# TPM.net
KiCad netlist of a schematic drawn in EAGLE
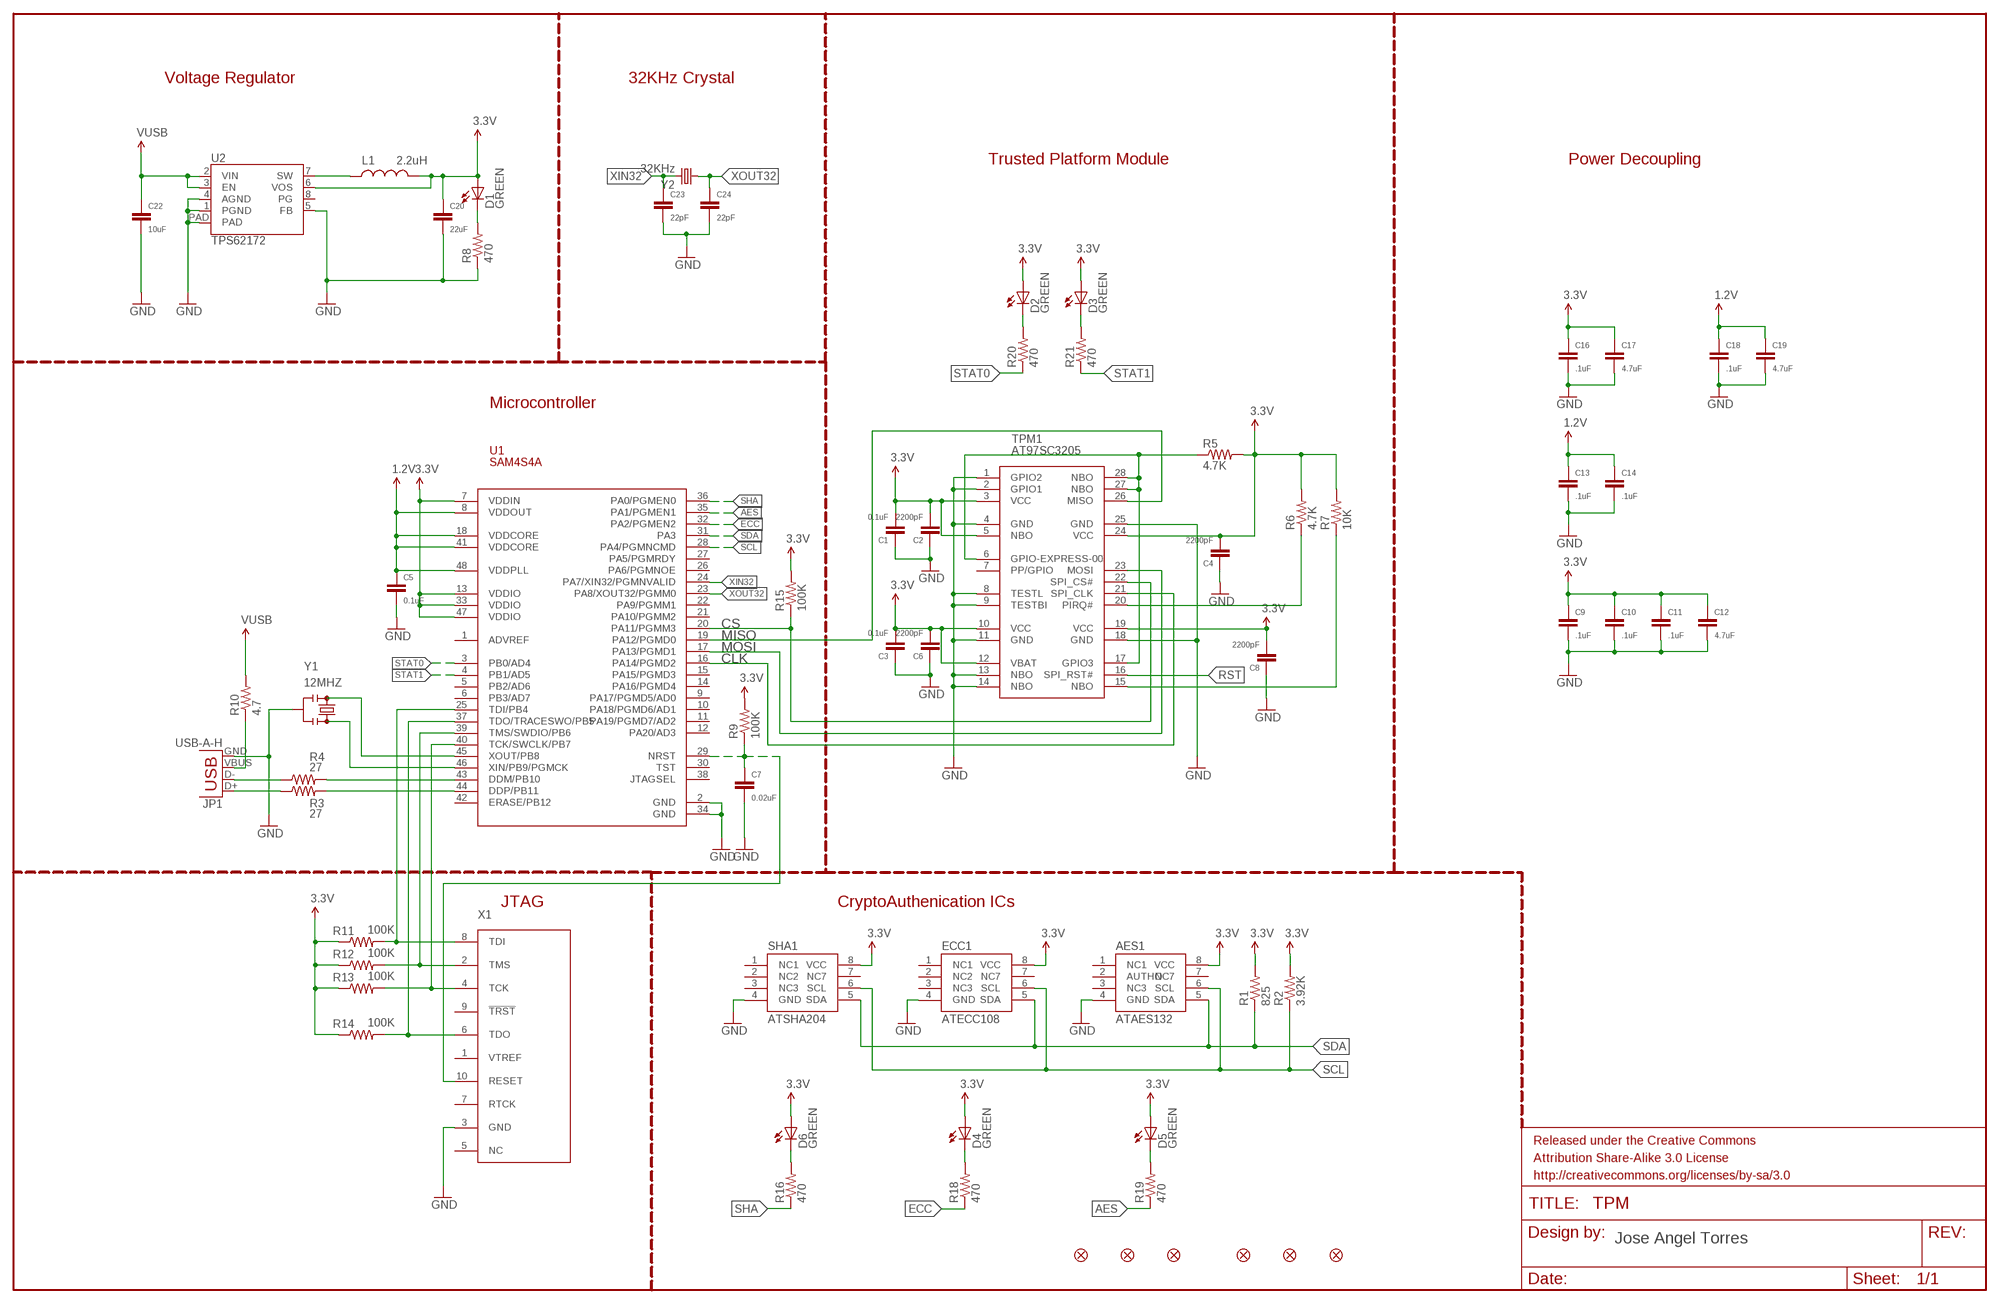
[diagram p0: schematic, sheet 1]

(export (version "E")
  (design (tool "Eeschema 10.0.6"))
  (components
    (comp (ref "AES1")
      (value "ATAES132")
      (footprint "eagle-import:CRYPTOTRONIX_SOIC8")
      (libsource (lib "eagle-import") (part "CRYPTOTRONIX_ATAES132"))
    )
    (comp (ref "C1")
      (value "0.1uF")
      (footprint "eagle-import:0201")
      (libsource (lib "eagle-import") (part "CAPACITOR.0201"))
    )
    (comp (ref "C2")
      (value "2200pF")
      (footprint "eagle-import:0201")
      (libsource (lib "eagle-import") (part "CAPACITOR.0201"))
    )
    (comp (ref "C3")
      (value "0.1uF")
      (footprint "eagle-import:0201")
      (libsource (lib "eagle-import") (part "CAPACITOR.0201"))
    )
    (comp (ref "C4")
      (value "2200pF")
      (footprint "eagle-import:0201")
      (libsource (lib "eagle-import") (part "CAPACITOR.0201"))
    )
    (comp (ref "C5")
      (value "0.1uF")
      (footprint "eagle-import:0201")
      (libsource (lib "eagle-import") (part "CAPACITOR.0201"))
    )
    (comp (ref "C6")
      (value "2200pF")
      (footprint "eagle-import:0201")
      (libsource (lib "eagle-import") (part "CAPACITOR.0201"))
    )
    (comp (ref "C7")
      (value "0.02uF")
      (footprint "eagle-import:0201")
      (libsource (lib "eagle-import") (part "CAPACITOR.0201"))
    )
    (comp (ref "C8")
      (value "2200pF")
      (footprint "eagle-import:0201")
      (libsource (lib "eagle-import") (part "CAPACITOR.0201"))
    )
    (comp (ref "C9")
      (value ".1uF")
      (footprint "eagle-import:0201")
      (libsource (lib "eagle-import") (part "CAPACITOR.0201"))
    )
    (comp (ref "C10")
      (value ".1uF")
      (footprint "eagle-import:0201")
      (libsource (lib "eagle-import") (part "CAPACITOR.0201"))
    )
    (comp (ref "C11")
      (value ".1uF")
      (footprint "eagle-import:0201")
      (libsource (lib "eagle-import") (part "CAPACITOR.0201"))
    )
    (comp (ref "C12")
      (value "4.7uF")
      (footprint "eagle-import:0402")
      (libsource (lib "eagle-import") (part "CAPACITOR.0402"))
    )
    (comp (ref "C13")
      (value ".1uF")
      (footprint "eagle-import:0201")
      (libsource (lib "eagle-import") (part "CAPACITOR.0201"))
    )
    (comp (ref "C14")
      (value ".1uF")
      (footprint "eagle-import:0201")
      (libsource (lib "eagle-import") (part "CAPACITOR.0201"))
    )
    (comp (ref "C16")
      (value ".1uF")
      (footprint "eagle-import:0201")
      (libsource (lib "eagle-import") (part "CAPACITOR.0201"))
    )
    (comp (ref "C17")
      (value "4.7uF")
      (footprint "eagle-import:0402")
      (libsource (lib "eagle-import") (part "CAPACITOR.0402"))
    )
    (comp (ref "C18")
      (value ".1uF")
      (footprint "eagle-import:0201")
      (libsource (lib "eagle-import") (part "CAPACITOR.0201"))
    )
    (comp (ref "C19")
      (value "4.7uF")
      (footprint "eagle-import:0402")
      (libsource (lib "eagle-import") (part "CAPACITOR.0402"))
    )
    (comp (ref "C20")
      (value "22uF")
      (footprint "eagle-import:0603")
      (libsource (lib "eagle-import") (part "CAPACITOR.0603"))
    )
    (comp (ref "C22")
      (value "10uF")
      (footprint "eagle-import:0402")
      (libsource (lib "eagle-import") (part "CAPACITOR.0402"))
    )
    (comp (ref "C23")
      (value "22pF")
      (footprint "eagle-import:0201")
      (libsource (lib "eagle-import") (part "CAPACITOR.0201"))
    )
    (comp (ref "C24")
      (value "22pF")
      (footprint "eagle-import:0201")
      (libsource (lib "eagle-import") (part "CAPACITOR.0201"))
    )
    (comp (ref "D1")
      (value "GREEN")
      (footprint "eagle-import:SPARKFUN-LED_LED-0603")
      (libsource (lib "eagle-import") (part "SPARKFUN-LED_LED-GREEN0603"))
    )
    (comp (ref "D2")
      (value "GREEN")
      (footprint "eagle-import:SPARKFUN-LED_LED-0603")
      (libsource (lib "eagle-import") (part "SPARKFUN-LED_LED-GREEN0603"))
    )
    (comp (ref "D3")
      (value "GREEN")
      (footprint "eagle-import:SPARKFUN-LED_LED-0603")
      (libsource (lib "eagle-import") (part "SPARKFUN-LED_LED-GREEN0603"))
    )
    (comp (ref "D4")
      (value "GREEN")
      (footprint "eagle-import:SPARKFUN-LED_LED-0603")
      (libsource (lib "eagle-import") (part "SPARKFUN-LED_LED-GREEN0603"))
    )
    (comp (ref "D5")
      (value "GREEN")
      (footprint "eagle-import:SPARKFUN-LED_LED-0603")
      (libsource (lib "eagle-import") (part "SPARKFUN-LED_LED-GREEN0603"))
    )
    (comp (ref "D6")
      (value "GREEN")
      (footprint "eagle-import:SPARKFUN-LED_LED-0603")
      (libsource (lib "eagle-import") (part "SPARKFUN-LED_LED-GREEN0603"))
    )
    (comp (ref "ECC1")
      (value "ATECC108")
      (footprint "eagle-import:CRYPTOTRONIX_SOIC8")
      (libsource (lib "eagle-import") (part "CRYPTOTRONIX_ATECC108"))
    )
    (comp (ref "FID1")
      (value "SPARKFUN-AESTHETICS_FIDUCIAL1X2.5")
      (footprint "eagle-import:SPARKFUN-AESTHETICS_FIDUCIAL-1X2.5")
      (libsource (lib "eagle-import") (part "SPARKFUN-AESTHETICS_FIDUCIAL1X2.5"))
    )
    (comp (ref "FID2")
      (value "SPARKFUN-AESTHETICS_FIDUCIAL1X2.5")
      (footprint "eagle-import:SPARKFUN-AESTHETICS_FIDUCIAL-1X2.5")
      (libsource (lib "eagle-import") (part "SPARKFUN-AESTHETICS_FIDUCIAL1X2.5"))
    )
    (comp (ref "FID3")
      (value "SPARKFUN-AESTHETICS_FIDUCIAL1X2.5")
      (footprint "eagle-import:SPARKFUN-AESTHETICS_FIDUCIAL-1X2.5")
      (libsource (lib "eagle-import") (part "SPARKFUN-AESTHETICS_FIDUCIAL1X2.5"))
    )
    (comp (ref "FID4")
      (value "SPARKFUN-AESTHETICS_FIDUCIAL1X2.5")
      (footprint "eagle-import:SPARKFUN-AESTHETICS_FIDUCIAL-1X2.5")
      (libsource (lib "eagle-import") (part "SPARKFUN-AESTHETICS_FIDUCIAL1X2.5"))
    )
    (comp (ref "FID5")
      (value "SPARKFUN-AESTHETICS_FIDUCIAL1X2.5")
      (footprint "eagle-import:SPARKFUN-AESTHETICS_FIDUCIAL-1X2.5")
      (libsource (lib "eagle-import") (part "SPARKFUN-AESTHETICS_FIDUCIAL1X2.5"))
    )
    (comp (ref "FID6")
      (value "SPARKFUN-AESTHETICS_FIDUCIAL1X2.5")
      (footprint "eagle-import:SPARKFUN-AESTHETICS_FIDUCIAL-1X2.5")
      (libsource (lib "eagle-import") (part "SPARKFUN-AESTHETICS_FIDUCIAL1X2.5"))
    )
    (comp (ref "JP1")
      (value "USB-A-H")
      (footprint "eagle-import:USB-A-H")
      (libsource (lib "eagle-import") (part "USB-A-H"))
    )
    (comp (ref "L1")
      (value "2.2uH")
      (footprint "eagle-import:C0402")
      (libsource (lib "eagle-import") (part "INDUCTOR0402"))
    )
    (comp (ref "R1")
      (value "825")
      (footprint "eagle-import:0201")
      (libsource (lib "eagle-import") (part "RESISTOR.0201"))
    )
    (comp (ref "R2")
      (value "3.92K")
      (footprint "eagle-import:0201")
      (libsource (lib "eagle-import") (part "RESISTOR.0201"))
    )
    (comp (ref "R3")
      (value "27")
      (footprint "eagle-import:0402")
      (libsource (lib "eagle-import") (part "RESISTOR.0402"))
    )
    (comp (ref "R4")
      (value "27")
      (footprint "eagle-import:0402")
      (libsource (lib "eagle-import") (part "RESISTOR.0402"))
    )
    (comp (ref "R5")
      (value "4.7K")
      (footprint "eagle-import:0201")
      (libsource (lib "eagle-import") (part "RESISTOR.0201"))
    )
    (comp (ref "R6")
      (value "4.7K")
      (footprint "eagle-import:0201")
      (libsource (lib "eagle-import") (part "RESISTOR.0201"))
    )
    (comp (ref "R7")
      (value "10K")
      (footprint "eagle-import:0201")
      (libsource (lib "eagle-import") (part "RESISTOR.0201"))
    )
    (comp (ref "R8")
      (value "470")
      (footprint "eagle-import:0402")
      (libsource (lib "eagle-import") (part "RESISTOR.0402"))
    )
    (comp (ref "R9")
      (value "100K")
      (footprint "eagle-import:0201")
      (libsource (lib "eagle-import") (part "RESISTOR.0201"))
    )
    (comp (ref "R10")
      (value "4.7")
      (footprint "eagle-import:0402")
      (libsource (lib "eagle-import") (part "RESISTOR.0402"))
    )
    (comp (ref "R11")
      (value "100K")
      (footprint "eagle-import:0201")
      (libsource (lib "eagle-import") (part "RESISTOR.0201"))
    )
    (comp (ref "R12")
      (value "100K")
      (footprint "eagle-import:0201")
      (libsource (lib "eagle-import") (part "RESISTOR.0201"))
    )
    (comp (ref "R13")
      (value "100K")
      (footprint "eagle-import:0201")
      (libsource (lib "eagle-import") (part "RESISTOR.0201"))
    )
    (comp (ref "R14")
      (value "100K")
      (footprint "eagle-import:0201")
      (libsource (lib "eagle-import") (part "RESISTOR.0201"))
    )
    (comp (ref "R15")
      (value "100K")
      (footprint "eagle-import:0201")
      (libsource (lib "eagle-import") (part "RESISTOR.0201"))
    )
    (comp (ref "R16")
      (value "470")
      (footprint "eagle-import:0201")
      (libsource (lib "eagle-import") (part "RESISTOR.0201"))
    )
    (comp (ref "R18")
      (value "470")
      (footprint "eagle-import:0201")
      (libsource (lib "eagle-import") (part "RESISTOR.0201"))
    )
    (comp (ref "R19")
      (value "470")
      (footprint "eagle-import:0201")
      (libsource (lib "eagle-import") (part "RESISTOR.0201"))
    )
    (comp (ref "R20")
      (value "470")
      (footprint "eagle-import:0201")
      (libsource (lib "eagle-import") (part "RESISTOR.0201"))
    )
    (comp (ref "R21")
      (value "470")
      (footprint "eagle-import:0201")
      (libsource (lib "eagle-import") (part "RESISTOR.0201"))
    )
    (comp (ref "SHA1")
      (value "ATSHA204")
      (footprint "eagle-import:CRYPTOTRONIX_SOIC8")
      (libsource (lib "eagle-import") (part "CRYPTOTRONIX_ATSHA204"))
    )
    (comp (ref "TPM1")
      (value "AT97SC3205")
      (footprint "eagle-import:TSSOP28")
      (libsource (lib "eagle-import") (part "AT97SC3205"))
    )
    (comp (ref "U1")
      (value "SAM4S4A")
      (footprint "eagle-import:LQFP-48")
      (libsource (lib "eagle-import") (part "SAM4S4A"))
    )
    (comp (ref "U2")
      (value "TPS62172")
      (footprint "eagle-import:WSON-8-PAD")
      (libsource (lib "eagle-import") (part "TPS62172"))
    )
    (comp (ref "X1")
      (value "TC2050-NL-MCP-NL")
      (footprint "eagle-import:TC2030-MCP-NL")
      (libsource (lib "eagle-import") (part "TC2050-NL-MCP-NL"))
    )
    (comp (ref "Y1")
      (value "12MHZ")
      (footprint "eagle-import:RESONATOR-SMD")
      (libsource (lib "eagle-import") (part "RESONATOR12MHZ"))
    )
    (comp (ref "Y2")
      (value "32KHz")
      (footprint "eagle-import:CRYSTAL-32KHZ-SMD_EPSON_MC146")
      (libsource (lib "eagle-import") (part "CRYSTALEPSONMC146"))
    )
  )
  (nets
    (net (code "1") (name "/CLK") (class "Default")
      (node (ref "TPM1") (pin "21") (pinfunction "SPI_CLK_21") (pintype "bidirectional"))
      (node (ref "U1") (pin "16") (pinfunction "PA14/PGMD2_16") (pintype "bidirectional"))
    )
    (net (code "2") (name "/CS") (class "Default")
      (node (ref "R15") (pin "1") (pinfunction "1_1") (pintype "passive"))
      (node (ref "TPM1") (pin "22") (pinfunction "SPI_CS#_22") (pintype "power_in"))
      (node (ref "U1") (pin "20") (pinfunction "PA11/PGMM3_20") (pintype "bidirectional"))
    )
    (net (code "3") (name "/MISO") (class "Default")
      (node (ref "TPM1") (pin "26") (pinfunction "MISO_26") (pintype "power_in"))
      (node (ref "U1") (pin "19") (pinfunction "PA12/PGMD0_19") (pintype "bidirectional"))
    )
    (net (code "4") (name "/MOSI") (class "Default")
      (node (ref "TPM1") (pin "23") (pinfunction "MOSI_23") (pintype "power_in"))
      (node (ref "U1") (pin "17") (pinfunction "PA13/PGMD1_17") (pintype "bidirectional"))
    )
    (net (code "5") (name "1.2V") (class "Default")
      (node (ref "C13") (pin "1") (pinfunction "1_1") (pintype "passive"))
      (node (ref "C14") (pin "1") (pinfunction "1_1") (pintype "passive"))
      (node (ref "C18") (pin "1") (pinfunction "1_1") (pintype "passive"))
      (node (ref "C19") (pin "1") (pinfunction "1_1") (pintype "passive"))
      (node (ref "C5") (pin "1") (pinfunction "1_1") (pintype "passive"))
      (node (ref "U1") (pin "18") (pinfunction "VDDCORE_18") (pintype "bidirectional"))
      (node (ref "U1") (pin "41") (pinfunction "VDDCORE_41") (pintype "bidirectional"))
      (node (ref "U1") (pin "48") (pinfunction "VDDPLL_48") (pintype "bidirectional"))
      (node (ref "U1") (pin "8") (pinfunction "VDDOUT_8") (pintype "bidirectional"))
    )
    (net (code "6") (name "3.3V") (class "Default")
      (node (ref "AES1") (pin "8") (pinfunction "VCC_8") (pintype "power_in"))
      (node (ref "C1") (pin "2") (pinfunction "2_2") (pintype "passive"))
      (node (ref "C10") (pin "1") (pinfunction "1_1") (pintype "passive"))
      (node (ref "C11") (pin "1") (pinfunction "1_1") (pintype "passive"))
      (node (ref "C12") (pin "1") (pinfunction "1_1") (pintype "passive"))
      (node (ref "C16") (pin "1") (pinfunction "1_1") (pintype "passive"))
      (node (ref "C17") (pin "1") (pinfunction "1_1") (pintype "passive"))
      (node (ref "C2") (pin "2") (pinfunction "2_2") (pintype "passive"))
      (node (ref "C20") (pin "1") (pinfunction "1_1") (pintype "passive"))
      (node (ref "C3") (pin "2") (pinfunction "2_2") (pintype "passive"))
      (node (ref "C4") (pin "2") (pinfunction "2_2") (pintype "passive"))
      (node (ref "C6") (pin "2") (pinfunction "2_2") (pintype "passive"))
      (node (ref "C8") (pin "2") (pinfunction "2_2") (pintype "passive"))
      (node (ref "C9") (pin "1") (pinfunction "1_1") (pintype "passive"))
      (node (ref "D1") (pin "A") (pinfunction "A_A") (pintype "passive"))
      (node (ref "D2") (pin "A") (pinfunction "A_A") (pintype "passive"))
      (node (ref "D3") (pin "A") (pinfunction "A_A") (pintype "passive"))
      (node (ref "D4") (pin "A") (pinfunction "A_A") (pintype "passive"))
      (node (ref "D5") (pin "A") (pinfunction "A_A") (pintype "passive"))
      (node (ref "D6") (pin "A") (pinfunction "A_A") (pintype "passive"))
      (node (ref "ECC1") (pin "8") (pinfunction "VCC_8") (pintype "power_in"))
      (node (ref "L1") (pin "2") (pinfunction "2_2") (pintype "passive"))
      (node (ref "R1") (pin "2") (pinfunction "2_2") (pintype "passive"))
      (node (ref "R11") (pin "1") (pinfunction "1_1") (pintype "passive"))
      (node (ref "R12") (pin "1") (pinfunction "1_1") (pintype "passive"))
      (node (ref "R13") (pin "1") (pinfunction "1_1") (pintype "passive"))
      (node (ref "R14") (pin "1") (pinfunction "1_1") (pintype "passive"))
      (node (ref "R15") (pin "2") (pinfunction "2_2") (pintype "passive"))
      (node (ref "R2") (pin "2") (pinfunction "2_2") (pintype "passive"))
      (node (ref "R5") (pin "2") (pinfunction "2_2") (pintype "passive"))
      (node (ref "R6") (pin "2") (pinfunction "2_2") (pintype "passive"))
      (node (ref "R7") (pin "2") (pinfunction "2_2") (pintype "passive"))
      (node (ref "R9") (pin "2") (pinfunction "2_2") (pintype "passive"))
      (node (ref "SHA1") (pin "8") (pinfunction "VCC_8") (pintype "power_in"))
      (node (ref "TPM1") (pin "10") (pinfunction "VCC_10") (pintype "power_in"))
      (node (ref "TPM1") (pin "12") (pinfunction "VBAT_12") (pintype "bidirectional"))
      (node (ref "TPM1") (pin "19") (pinfunction "VCC_19") (pintype "power_in"))
      (node (ref "TPM1") (pin "24") (pinfunction "VCC_24") (pintype "power_in"))
      (node (ref "TPM1") (pin "3") (pinfunction "VCC_3") (pintype "power_in"))
      (node (ref "TPM1") (pin "5") (pinfunction "NBO_5") (pintype "bidirectional"))
      (node (ref "U1") (pin "13") (pinfunction "VDDIO_13") (pintype "bidirectional"))
      (node (ref "U1") (pin "33") (pinfunction "VDDIO_33") (pintype "bidirectional"))
      (node (ref "U1") (pin "47") (pinfunction "VDDIO_47") (pintype "bidirectional"))
      (node (ref "U1") (pin "7") (pinfunction "VDDIN_7") (pintype "bidirectional"))
      (node (ref "U2") (pin "6") (pinfunction "VOS_6") (pintype "bidirectional"))
    )
    (net (code "7") (name "AES") (class "Default")
      (node (ref "R19") (pin "1") (pinfunction "1_1") (pintype "passive"))
      (node (ref "U1") (pin "35") (pinfunction "PA1/PGMEN1_35") (pintype "bidirectional"))
    )
    (net (code "8") (name "ECC") (class "Default")
      (node (ref "R18") (pin "1") (pinfunction "1_1") (pintype "passive"))
      (node (ref "U1") (pin "32") (pinfunction "PA2/PGMEN2_32") (pintype "bidirectional"))
    )
    (net (code "9") (name "GND") (class "Default")
      (node (ref "AES1") (pin "4") (pinfunction "GND_4") (pintype "power_in"))
      (node (ref "C1") (pin "1") (pinfunction "1_1") (pintype "passive"))
      (node (ref "C10") (pin "2") (pinfunction "2_2") (pintype "passive"))
      (node (ref "C11") (pin "2") (pinfunction "2_2") (pintype "passive"))
      (node (ref "C12") (pin "2") (pinfunction "2_2") (pintype "passive"))
      (node (ref "C13") (pin "2") (pinfunction "2_2") (pintype "passive"))
      (node (ref "C14") (pin "2") (pinfunction "2_2") (pintype "passive"))
      (node (ref "C16") (pin "2") (pinfunction "2_2") (pintype "passive"))
      (node (ref "C17") (pin "2") (pinfunction "2_2") (pintype "passive"))
      (node (ref "C18") (pin "2") (pinfunction "2_2") (pintype "passive"))
      (node (ref "C19") (pin "2") (pinfunction "2_2") (pintype "passive"))
      (node (ref "C2") (pin "1") (pinfunction "1_1") (pintype "passive"))
      (node (ref "C20") (pin "2") (pinfunction "2_2") (pintype "passive"))
      (node (ref "C22") (pin "2") (pinfunction "2_2") (pintype "passive"))
      (node (ref "C23") (pin "2") (pinfunction "2_2") (pintype "passive"))
      (node (ref "C24") (pin "2") (pinfunction "2_2") (pintype "passive"))
      (node (ref "C3") (pin "1") (pinfunction "1_1") (pintype "passive"))
      (node (ref "C4") (pin "1") (pinfunction "1_1") (pintype "passive"))
      (node (ref "C5") (pin "2") (pinfunction "2_2") (pintype "passive"))
      (node (ref "C6") (pin "1") (pinfunction "1_1") (pintype "passive"))
      (node (ref "C7") (pin "2") (pinfunction "2_2") (pintype "passive"))
      (node (ref "C8") (pin "1") (pinfunction "1_1") (pintype "passive"))
      (node (ref "C9") (pin "2") (pinfunction "2_2") (pintype "passive"))
      (node (ref "ECC1") (pin "4") (pinfunction "GND_4") (pintype "power_in"))
      (node (ref "JP1") (pin "GND") (pinfunction "GND_GND") (pintype "bidirectional"))
      (node (ref "R8") (pin "1") (pinfunction "1_1") (pintype "passive"))
      (node (ref "SHA1") (pin "4") (pinfunction "GND_4") (pintype "power_in"))
      (node (ref "TPM1") (pin "1") (pinfunction "GPIO2_1") (pintype "bidirectional"))
      (node (ref "TPM1") (pin "11") (pinfunction "GND_11") (pintype "power_in"))
      (node (ref "TPM1") (pin "13") (pinfunction "NBO_13") (pintype "bidirectional"))
      (node (ref "TPM1") (pin "14") (pinfunction "NBO_14") (pintype "bidirectional"))
      (node (ref "TPM1") (pin "18") (pinfunction "GND_18") (pintype "power_in"))
      (node (ref "TPM1") (pin "2") (pinfunction "GPIO1_2") (pintype "bidirectional"))
      (node (ref "TPM1") (pin "25") (pinfunction "GND_25") (pintype "power_in"))
      (node (ref "TPM1") (pin "4") (pinfunction "GND_4") (pintype "power_in"))
      (node (ref "TPM1") (pin "8") (pinfunction "TESTL_8") (pintype "bidirectional"))
      (node (ref "TPM1") (pin "9") (pinfunction "TESTBI_9") (pintype "bidirectional"))
      (node (ref "U1") (pin "2") (pinfunction "GND_2") (pintype "bidirectional"))
      (node (ref "U1") (pin "34") (pinfunction "GND_34") (pintype "bidirectional"))
      (node (ref "U2") (pin "1") (pinfunction "PGND_1") (pintype "bidirectional"))
      (node (ref "U2") (pin "4") (pinfunction "AGND_4") (pintype "bidirectional"))
      (node (ref "U2") (pin "5") (pinfunction "FB_5") (pintype "bidirectional"))
      (node (ref "U2") (pin "PAD") (pinfunction "PAD_PAD") (pintype "bidirectional"))
      (node (ref "X1") (pin "3") (pinfunction "GND_3") (pintype "bidirectional"))
      (node (ref "Y1") (pin "2") (pinfunction "2_2") (pintype "passive"))
    )
    (net (code "10") (name "Net-(D1-PadC)") (class "Default")
      (node (ref "D1") (pin "C") (pinfunction "C_C") (pintype "passive"))
      (node (ref "R8") (pin "2") (pinfunction "2_2") (pintype "passive"))
    )
    (net (code "11") (name "Net-(D2-PadC)") (class "Default")
      (node (ref "D2") (pin "C") (pinfunction "C_C") (pintype "passive"))
      (node (ref "R20") (pin "2") (pinfunction "2_2") (pintype "passive"))
    )
    (net (code "12") (name "Net-(D3-PadC)") (class "Default")
      (node (ref "D3") (pin "C") (pinfunction "C_C") (pintype "passive"))
      (node (ref "R21") (pin "2") (pinfunction "2_2") (pintype "passive"))
    )
    (net (code "13") (name "Net-(D4-PadC)") (class "Default")
      (node (ref "D4") (pin "C") (pinfunction "C_C") (pintype "passive"))
      (node (ref "R18") (pin "2") (pinfunction "2_2") (pintype "passive"))
    )
    (net (code "14") (name "Net-(D5-PadC)") (class "Default")
      (node (ref "D5") (pin "C") (pinfunction "C_C") (pintype "passive"))
      (node (ref "R19") (pin "2") (pinfunction "2_2") (pintype "passive"))
    )
    (net (code "15") (name "Net-(D6-PadC)") (class "Default")
      (node (ref "D6") (pin "C") (pinfunction "C_C") (pintype "passive"))
      (node (ref "R16") (pin "2") (pinfunction "2_2") (pintype "passive"))
    )
    (net (code "16") (name "Net-(JP1-PadD+)") (class "Default")
      (node (ref "JP1") (pin "D+") (pinfunction "D+_D+") (pintype "bidirectional"))
      (node (ref "R3") (pin "1") (pinfunction "1_1") (pintype "passive"))
    )
    (net (code "17") (name "Net-(JP1-PadD-)") (class "Default")
      (node (ref "JP1") (pin "D-") (pinfunction "D-_D-") (pintype "bidirectional"))
      (node (ref "R4") (pin "1") (pinfunction "1_1") (pintype "passive"))
    )
    (net (code "18") (name "Net-(JP1-PadVBUS)") (class "Default")
      (node (ref "JP1") (pin "VBUS") (pinfunction "VBUS_VBUS") (pintype "bidirectional"))
      (node (ref "R10") (pin "1") (pinfunction "1_1") (pintype "passive"))
    )
    (net (code "19") (name "Net-(R7-Pad1)") (class "Default")
      (node (ref "R7") (pin "1") (pinfunction "1_1") (pintype "passive"))
      (node (ref "TPM1") (pin "15") (pinfunction "NBO_15") (pintype "bidirectional"))
    )
    (net (code "20") (name "Net-(TPM1-GPIO-EXPRESS-00)") (class "Default")
      (node (ref "R5") (pin "1") (pinfunction "1_1") (pintype "passive"))
      (node (ref "TPM1") (pin "17") (pinfunction "GPIO3_17") (pintype "power_in"))
      (node (ref "TPM1") (pin "27") (pinfunction "NBO_27") (pintype "bidirectional"))
      (node (ref "TPM1") (pin "28") (pinfunction "NBO_28") (pintype "bidirectional"))
      (node (ref "TPM1") (pin "6") (pinfunction "GPIO-EXPRESS-00_6") (pintype "power_in"))
    )
    (net (code "21") (name "Net-(TPM1-PIRQ#)") (class "Default")
      (node (ref "R6") (pin "1") (pinfunction "1_1") (pintype "passive"))
      (node (ref "TPM1") (pin "20") (pinfunction "PIRQ#_20") (pintype "power_in"))
    )
    (net (code "22") (name "Net-(U1-DDM{slash}PB10)") (class "Default")
      (node (ref "R4") (pin "2") (pinfunction "2_2") (pintype "passive"))
      (node (ref "U1") (pin "43") (pinfunction "DDM/PB10_43") (pintype "bidirectional"))
    )
    (net (code "23") (name "Net-(U1-DDP{slash}PB11)") (class "Default")
      (node (ref "R3") (pin "2") (pinfunction "2_2") (pintype "passive"))
      (node (ref "U1") (pin "44") (pinfunction "DDP/PB11_44") (pintype "bidirectional"))
    )
    (net (code "24") (name "Net-(U1-TCK{slash}SWCLK{slash}PB7)") (class "Default")
      (node (ref "R13") (pin "2") (pinfunction "2_2") (pintype "passive"))
      (node (ref "U1") (pin "40") (pinfunction "TCK/SWCLK/PB7_40") (pintype "bidirectional"))
      (node (ref "X1") (pin "4") (pinfunction "TCK_4") (pintype "bidirectional"))
    )
    (net (code "25") (name "Net-(U1-TDI{slash}PB4)") (class "Default")
      (node (ref "R11") (pin "2") (pinfunction "2_2") (pintype "passive"))
      (node (ref "U1") (pin "25") (pinfunction "TDI/PB4_25") (pintype "bidirectional"))
      (node (ref "X1") (pin "8") (pinfunction "TDI_8") (pintype "bidirectional"))
    )
    (net (code "26") (name "Net-(U1-TDO{slash}TRACESWO{slash}PB5)") (class "Default")
      (node (ref "R14") (pin "2") (pinfunction "2_2") (pintype "passive"))
      (node (ref "U1") (pin "37") (pinfunction "TDO/TRACESWO/PB5_37") (pintype "bidirectional"))
      (node (ref "X1") (pin "6") (pinfunction "TDO_6") (pintype "bidirectional"))
    )
    (net (code "27") (name "Net-(U1-TMS{slash}SWDIO{slash}PB6)") (class "Default")
      (node (ref "R12") (pin "2") (pinfunction "2_2") (pintype "passive"))
      (node (ref "U1") (pin "39") (pinfunction "TMS/SWDIO/PB6_39") (pintype "bidirectional"))
      (node (ref "X1") (pin "2") (pinfunction "TMS_2") (pintype "bidirectional"))
    )
    (net (code "28") (name "Net-(U1-XIN{slash}PB9{slash}PGMCK)") (class "Default")
      (node (ref "U1") (pin "46") (pinfunction "XIN/PB9/PGMCK_46") (pintype "bidirectional"))
      (node (ref "Y1") (pin "3") (pinfunction "3_3") (pintype "passive"))
    )
    (net (code "29") (name "Net-(U1-XOUT{slash}PB8)") (class "Default")
      (node (ref "U1") (pin "45") (pinfunction "XOUT/PB8_45") (pintype "bidirectional"))
      (node (ref "Y1") (pin "1") (pinfunction "1_1") (pintype "passive"))
    )
    (net (code "30") (name "Net-(U2-SW)") (class "Default")
      (node (ref "L1") (pin "1") (pinfunction "1_1") (pintype "passive"))
      (node (ref "U2") (pin "7") (pinfunction "SW_7") (pintype "bidirectional"))
    )
    (net (code "31") (name "RST") (class "Default")
      (node (ref "C7") (pin "1") (pinfunction "1_1") (pintype "passive"))
      (node (ref "R9") (pin "1") (pinfunction "1_1") (pintype "passive"))
      (node (ref "TPM1") (pin "16") (pinfunction "SPI_RST#_16") (pintype "bidirectional"))
      (node (ref "U1") (pin "29") (pinfunction "NRST_29") (pintype "bidirectional"))
      (node (ref "X1") (pin "10") (pinfunction "RESET_10") (pintype "bidirectional"))
    )
    (net (code "32") (name "SCL") (class "Default")
      (node (ref "AES1") (pin "6") (pinfunction "SCL_6") (pintype "bidirectional"))
      (node (ref "ECC1") (pin "6") (pinfunction "SCL_6") (pintype "bidirectional"))
      (node (ref "R2") (pin "1") (pinfunction "1_1") (pintype "passive"))
      (node (ref "SHA1") (pin "6") (pinfunction "SCL_6") (pintype "bidirectional"))
      (node (ref "U1") (pin "28") (pinfunction "PA4/PGMNCMD_28") (pintype "bidirectional"))
    )
    (net (code "33") (name "SDA") (class "Default")
      (node (ref "AES1") (pin "5") (pinfunction "SDA_5") (pintype "bidirectional"))
      (node (ref "ECC1") (pin "5") (pinfunction "SDA_5") (pintype "bidirectional"))
      (node (ref "R1") (pin "1") (pinfunction "1_1") (pintype "passive"))
      (node (ref "SHA1") (pin "5") (pinfunction "SDA_5") (pintype "bidirectional"))
      (node (ref "U1") (pin "31") (pinfunction "PA3_31") (pintype "bidirectional"))
    )
    (net (code "34") (name "SHA") (class "Default")
      (node (ref "R16") (pin "1") (pinfunction "1_1") (pintype "passive"))
      (node (ref "U1") (pin "36") (pinfunction "PA0/PGMEN0_36") (pintype "bidirectional"))
    )
    (net (code "35") (name "STAT0") (class "Default")
      (node (ref "R20") (pin "1") (pinfunction "1_1") (pintype "passive"))
      (node (ref "U1") (pin "3") (pinfunction "PB0/AD4_3") (pintype "bidirectional"))
    )
    (net (code "36") (name "STAT1") (class "Default")
      (node (ref "R21") (pin "1") (pinfunction "1_1") (pintype "passive"))
      (node (ref "U1") (pin "4") (pinfunction "PB1/AD5_4") (pintype "bidirectional"))
    )
    (net (code "37") (name "VUSB") (class "Default")
      (node (ref "C22") (pin "1") (pinfunction "1_1") (pintype "passive"))
      (node (ref "R10") (pin "2") (pinfunction "2_2") (pintype "passive"))
      (node (ref "U2") (pin "2") (pinfunction "VIN_2") (pintype "bidirectional"))
      (node (ref "U2") (pin "3") (pinfunction "EN_3") (pintype "bidirectional"))
    )
    (net (code "38") (name "XIN32") (class "Default")
      (node (ref "C23") (pin "1") (pinfunction "1_1") (pintype "passive"))
      (node (ref "U1") (pin "24") (pinfunction "PA7/XIN32/PGMNVALID_24") (pintype "bidirectional"))
      (node (ref "Y2") (pin "P$1") (pinfunction "2_P$1") (pintype "passive"))
    )
    (net (code "39") (name "XOUT32") (class "Default")
      (node (ref "C24") (pin "1") (pinfunction "1_1") (pintype "passive"))
      (node (ref "U1") (pin "23") (pinfunction "PA8/XOUT32/PGMM0_23") (pintype "bidirectional"))
      (node (ref "Y2") (pin "P$2") (pinfunction "1_P$2") (pintype "passive"))
    )
    (net (code "40") (name "unconnected-(AES1-AUTHO-Pad2)") (class "Default")
      (node (ref "AES1") (pin "2") (pinfunction "AUTHO_2") (pintype "bidirectional"))
    )
    (net (code "41") (name "unconnected-(AES1-NC1-Pad1)") (class "Default")
      (node (ref "AES1") (pin "1") (pinfunction "NC1_1") (pintype "no_connect"))
    )
    (net (code "42") (name "unconnected-(AES1-NC3-Pad3)") (class "Default")
      (node (ref "AES1") (pin "3") (pinfunction "NC3_3") (pintype "no_connect"))
    )
    (net (code "43") (name "unconnected-(AES1-NC7-Pad7)") (class "Default")
      (node (ref "AES1") (pin "7") (pinfunction "NC7_7") (pintype "no_connect"))
    )
    (net (code "44") (name "unconnected-(ECC1-NC1-Pad1)") (class "Default")
      (node (ref "ECC1") (pin "1") (pinfunction "NC1_1") (pintype "bidirectional"))
    )
    (net (code "45") (name "unconnected-(ECC1-NC2-Pad2)") (class "Default")
      (node (ref "ECC1") (pin "2") (pinfunction "NC2_2") (pintype "no_connect"))
    )
    (net (code "46") (name "unconnected-(ECC1-NC3-Pad3)") (class "Default")
      (node (ref "ECC1") (pin "3") (pinfunction "NC3_3") (pintype "no_connect"))
    )
    (net (code "47") (name "unconnected-(ECC1-NC7-Pad7)") (class "Default")
      (node (ref "ECC1") (pin "7") (pinfunction "NC7_7") (pintype "no_connect"))
    )
    (net (code "48") (name "unconnected-(SHA1-NC1-Pad1)") (class "Default")
      (node (ref "SHA1") (pin "1") (pinfunction "NC1_1") (pintype "no_connect"))
    )
    (net (code "49") (name "unconnected-(SHA1-NC2-Pad2)") (class "Default")
      (node (ref "SHA1") (pin "2") (pinfunction "NC2_2") (pintype "no_connect"))
    )
    (net (code "50") (name "unconnected-(SHA1-NC3-Pad3)") (class "Default")
      (node (ref "SHA1") (pin "3") (pinfunction "NC3_3") (pintype "no_connect"))
    )
    (net (code "51") (name "unconnected-(SHA1-NC7-Pad7)") (class "Default")
      (node (ref "SHA1") (pin "7") (pinfunction "NC7_7") (pintype "no_connect"))
    )
    (net (code "52") (name "unconnected-(TPM1-PP{slash}GPIO-Pad7)") (class "Default")
      (node (ref "TPM1") (pin "7") (pinfunction "PP/GPIO_7") (pintype "bidirectional"))
    )
    (net (code "53") (name "unconnected-(U1-ADVREF-Pad1)") (class "Default")
      (node (ref "U1") (pin "1") (pinfunction "ADVREF_1") (pintype "bidirectional"))
    )
    (net (code "54") (name "unconnected-(U1-ERASE{slash}PB12-Pad42)") (class "Default")
      (node (ref "U1") (pin "42") (pinfunction "ERASE/PB12_42") (pintype "bidirectional"))
    )
    (net (code "55") (name "unconnected-(U1-JTAGSEL-Pad38)") (class "Default")
      (node (ref "U1") (pin "38") (pinfunction "JTAGSEL_38") (pintype "bidirectional"))
    )
    (net (code "56") (name "unconnected-(U1-PA5{slash}PGMRDY-Pad27)") (class "Default")
      (node (ref "U1") (pin "27") (pinfunction "PA5/PGMRDY_27") (pintype "bidirectional"))
    )
    (net (code "57") (name "unconnected-(U1-PA6{slash}PGMNOE-Pad26)") (class "Default")
      (node (ref "U1") (pin "26") (pinfunction "PA6/PGMNOE_26") (pintype "bidirectional"))
    )
    (net (code "58") (name "unconnected-(U1-PA9{slash}PGMM1-Pad22)") (class "Default")
      (node (ref "U1") (pin "22") (pinfunction "PA9/PGMM1_22") (pintype "bidirectional"))
    )
    (net (code "59") (name "unconnected-(U1-PA10{slash}PGMM2-Pad21)") (class "Default")
      (node (ref "U1") (pin "21") (pinfunction "PA10/PGMM2_21") (pintype "bidirectional"))
    )
    (net (code "60") (name "unconnected-(U1-PA15{slash}PGMD3-Pad15)") (class "Default")
      (node (ref "U1") (pin "15") (pinfunction "PA15/PGMD3_15") (pintype "bidirectional"))
    )
    (net (code "61") (name "unconnected-(U1-PA16{slash}PGMD4-Pad14)") (class "Default")
      (node (ref "U1") (pin "14") (pinfunction "PA16/PGMD4_14") (pintype "bidirectional"))
    )
    (net (code "62") (name "unconnected-(U1-PA17{slash}PGMD5{slash}AD0-Pad9)") (class "Default")
      (node (ref "U1") (pin "9") (pinfunction "PA17/PGMD5/AD0_9") (pintype "bidirectional"))
    )
    (net (code "63") (name "unconnected-(U1-PA18{slash}PGMD6{slash}AD1-Pad10)") (class "Default")
      (node (ref "U1") (pin "10") (pinfunction "PA18/PGMD6/AD1_10") (pintype "bidirectional"))
    )
    (net (code "64") (name "unconnected-(U1-PA19{slash}PGMD7{slash}AD2-Pad11)") (class "Default")
      (node (ref "U1") (pin "11") (pinfunction "PA19/PGMD7/AD2_11") (pintype "bidirectional"))
    )
    (net (code "65") (name "unconnected-(U1-PA20{slash}AD3-Pad12)") (class "Default")
      (node (ref "U1") (pin "12") (pinfunction "PA20/AD3_12") (pintype "bidirectional"))
    )
    (net (code "66") (name "unconnected-(U1-PB2{slash}AD6-Pad5)") (class "Default")
      (node (ref "U1") (pin "5") (pinfunction "PB2/AD6_5") (pintype "bidirectional"))
    )
    (net (code "67") (name "unconnected-(U1-PB3{slash}AD7-Pad6)") (class "Default")
      (node (ref "U1") (pin "6") (pinfunction "PB3/AD7_6") (pintype "bidirectional"))
    )
    (net (code "68") (name "unconnected-(U1-TST-Pad30)") (class "Default")
      (node (ref "U1") (pin "30") (pinfunction "TST_30") (pintype "bidirectional"))
    )
    (net (code "69") (name "unconnected-(U2-PG-Pad8)") (class "Default")
      (node (ref "U2") (pin "8") (pinfunction "PG_8") (pintype "bidirectional"))
    )
    (net (code "70") (name "unconnected-(X1-NC-Pad5)") (class "Default")
      (node (ref "X1") (pin "5") (pinfunction "NC_5") (pintype "bidirectional"))
    )
    (net (code "71") (name "unconnected-(X1-RTCK-Pad7)") (class "Default")
      (node (ref "X1") (pin "7") (pinfunction "RTCK_7") (pintype "bidirectional"))
    )
    (net (code "72") (name "unconnected-(X1-VTREF-Pad1)") (class "Default")
      (node (ref "X1") (pin "1") (pinfunction "VTREF_1") (pintype "bidirectional"))
    )
    (net (code "73") (name "unconnected-(X1-~{TRST}-Pad9)") (class "Default")
      (node (ref "X1") (pin "9") (pinfunction "~{TRST}_9") (pintype "bidirectional"))
    )
  )
)
